# Sch_Sheet_Template.net
KiCad netlist of a schematic drawn in Altium Designer
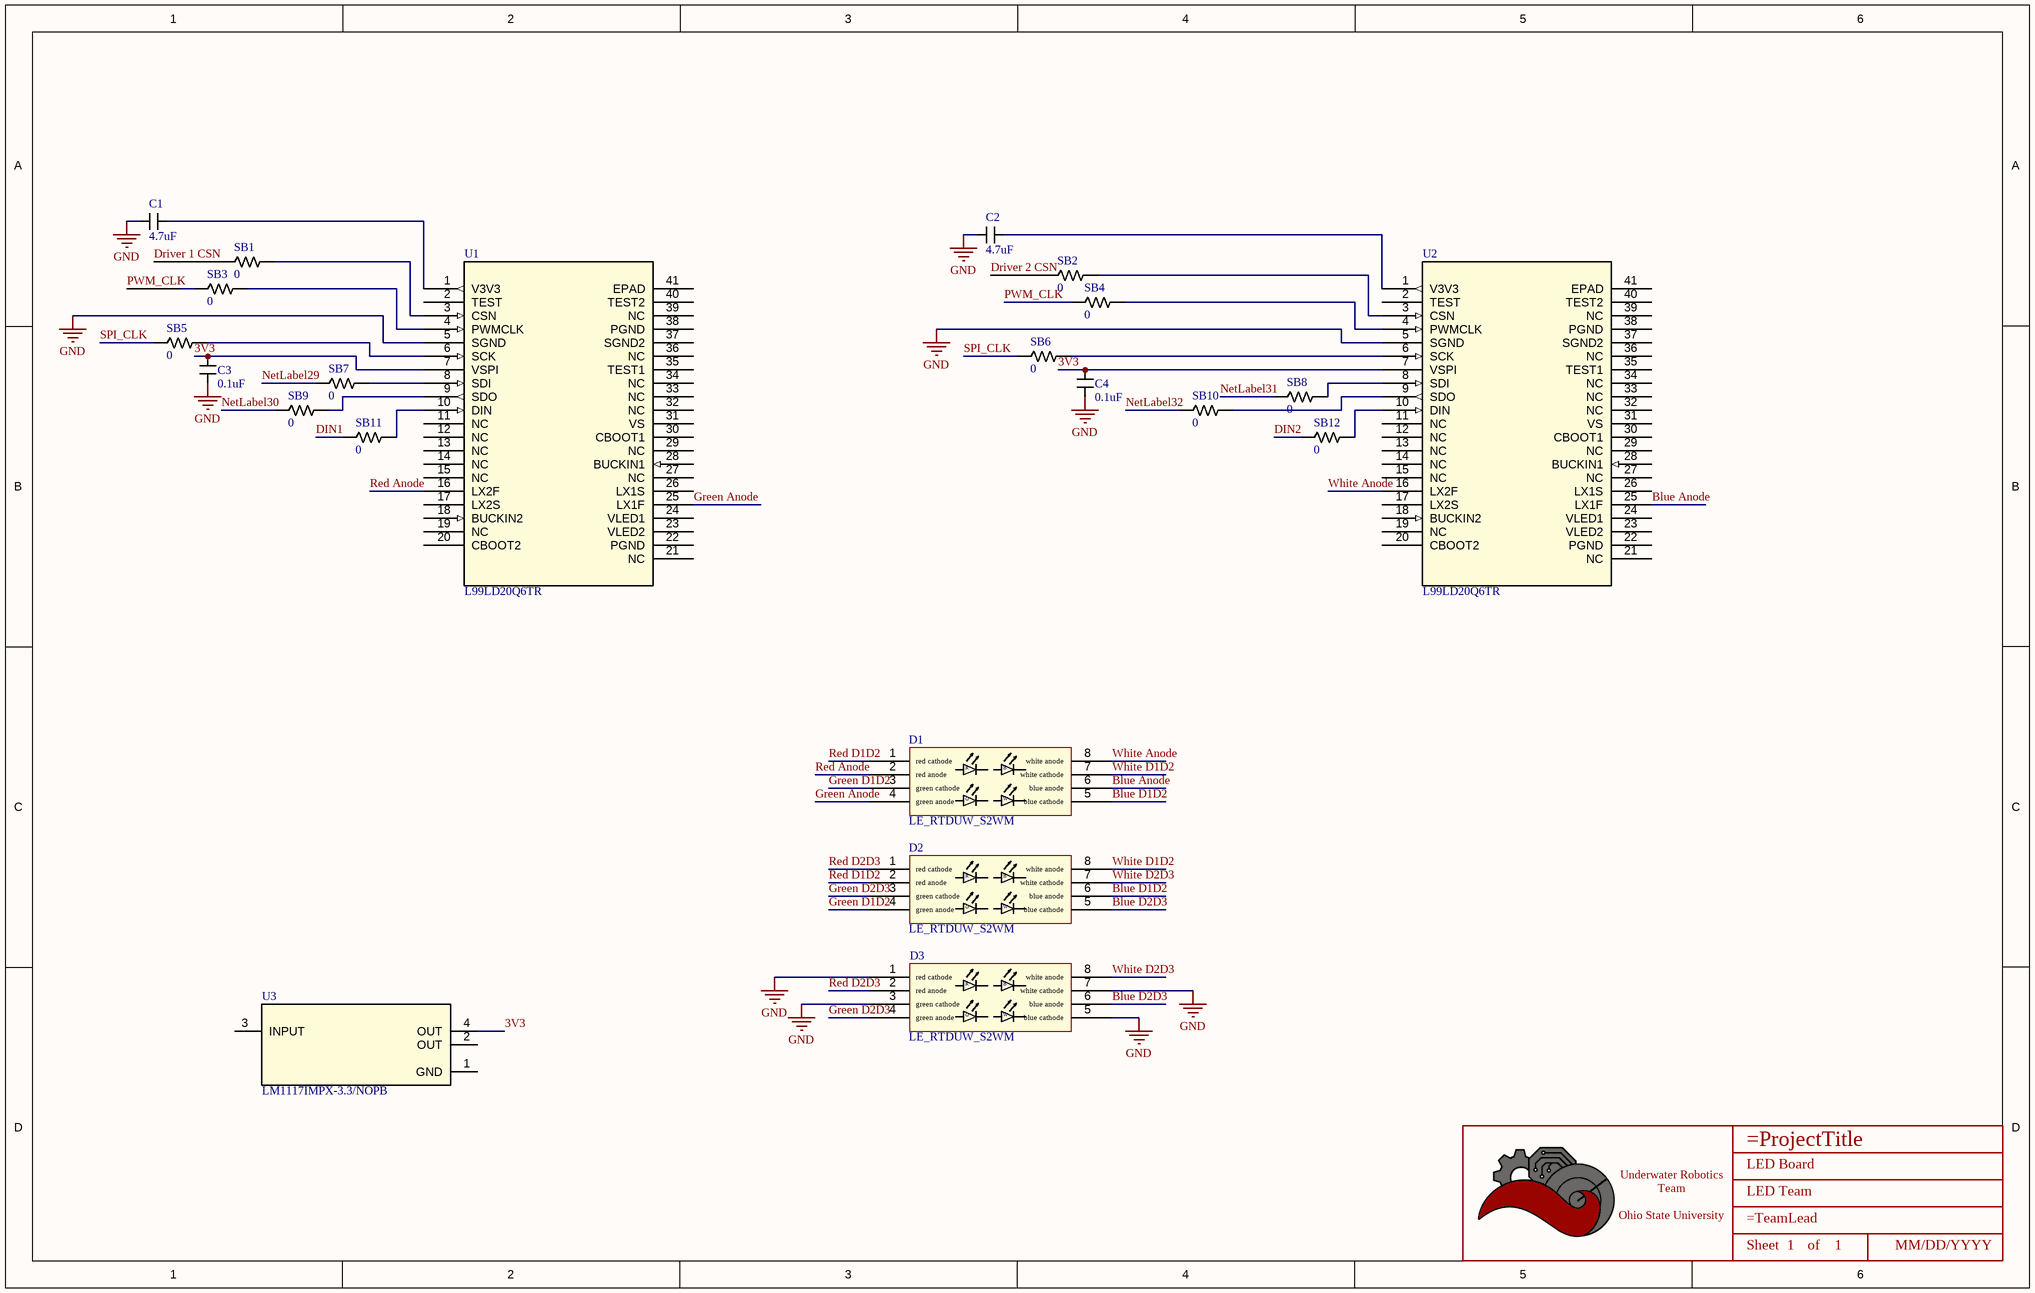
[diagram p0: Sch_Sheet_Template.SchDoc]

(export (version "E")
  (design (tool "Eeschema 10.0.6"))
  (components
    (comp (ref "*")
      (value "Title_Block")
      (footprint "LOGO")
      (description "UWRT Schematic Title Block Template\r\n\r\nCreated June 2021, Dylan Trainor")
      (libsource (lib "UWRT") (part "Title_Block"))
    )
    (comp (ref "C1")
      (value "4.7uF")
      (footprint "CAPACITOR_0603")
      (description "Cap 4.7uF 6.3V +/-10%\r\nCeramic 0603")
      (fields
        (field (name "TOLERANCE") "+/- 10%")
        (field (name "VOLTAGE") "6.3V")
        (field (name "MADE BY") "Robert Pafford")
      )
      (libsource (lib "Capacitors") (part "CAPACITOR_4.7uF_0603"))
    )
    (comp (ref "C2")
      (value "4.7uF")
      (footprint "CAPACITOR_0603")
      (description "Cap 4.7uF 6.3V +/-10%\r\nCeramic 0603")
      (fields
        (field (name "TOLERANCE") "+/- 10%")
        (field (name "VOLTAGE") "6.3V")
        (field (name "MADE BY") "Robert Pafford")
      )
      (libsource (lib "Capacitors") (part "CAPACITOR_4.7uF_0603"))
    )
    (comp (ref "C3")
      (value "0.1uF")
      (footprint "CAPACITOR_0603")
      (description "Cap 100nF 6.3V +/-10%\r\nCeramic 0603")
      (fields
        (field (name "TOLERANCE") "+/- 10%")
        (field (name "VOLTAGE") "6.3V")
        (field (name "MADE BY") "Flip B")
      )
      (libsource (lib "Capacitors") (part "CAPACITOR_0.1uF_0603_1"))
    )
    (comp (ref "C4")
      (value "0.1uF")
      (footprint "CAPACITOR_0603")
      (description "Cap 100nF 6.3V +/-10%\r\nCeramic 0603")
      (fields
        (field (name "TOLERANCE") "+/- 10%")
        (field (name "VOLTAGE") "6.3V")
        (field (name "MADE BY") "Flip B")
      )
      (libsource (lib "Capacitors") (part "CAPACITOR_0.1uF_0603_1"))
    )
    (comp (ref "D1")
      (value "LE_RTDUW_S2WM")
      (description "LED OSTAR RGBW 625/527/453NM SMD")
      (libsource (lib "Diodes") (part "LE_RTDUW_S2WM"))
    )
    (comp (ref "D2")
      (value "LE_RTDUW_S2WM")
      (description "LED OSTAR RGBW 625/527/453NM SMD")
      (libsource (lib "Diodes") (part "LE_RTDUW_S2WM"))
    )
    (comp (ref "D3")
      (value "LE_RTDUW_S2WM")
      (description "LED OSTAR RGBW 625/527/453NM SMD")
      (libsource (lib "Diodes") (part "LE_RTDUW_S2WM"))
    )
    (comp (ref "SB1")
      (value "0 Ohm Jumper No Fit")
      (footprint "RESISTOR_0603")
      (description "0 Ohm Jumper No Fit for Solder Bridge")
      (fields (field (name "VALUE  (OHMS)") "0") (field (name "MADE BY") "Robert Pafford"))
      (libsource (lib "Resistors") (part "JUMPER_0_0603"))
    )
    (comp (ref "SB2")
      (value "0 Ohm Jumper No Fit")
      (footprint "RESISTOR_0603")
      (description "0 Ohm Jumper No Fit for Solder Bridge")
      (fields (field (name "VALUE  (OHMS)") "0") (field (name "MADE BY") "Robert Pafford"))
      (libsource (lib "Resistors") (part "JUMPER_0_0603"))
    )
    (comp (ref "SB3")
      (value "0 Ohm Jumper No Fit")
      (footprint "RESISTOR_0603")
      (description "0 Ohm Jumper No Fit for Solder Bridge")
      (fields (field (name "VALUE  (OHMS)") "0") (field (name "MADE BY") "Robert Pafford"))
      (libsource (lib "Resistors") (part "JUMPER_0_0603"))
    )
    (comp (ref "SB4")
      (value "0 Ohm Jumper No Fit")
      (footprint "RESISTOR_0603")
      (description "0 Ohm Jumper No Fit for Solder Bridge")
      (fields (field (name "VALUE  (OHMS)") "0") (field (name "MADE BY") "Robert Pafford"))
      (libsource (lib "Resistors") (part "JUMPER_0_0603"))
    )
    (comp (ref "SB5")
      (value "0 Ohm Jumper No Fit")
      (footprint "RESISTOR_0603")
      (description "0 Ohm Jumper No Fit for Solder Bridge")
      (fields (field (name "VALUE  (OHMS)") "0") (field (name "MADE BY") "Robert Pafford"))
      (libsource (lib "Resistors") (part "JUMPER_0_0603"))
    )
    (comp (ref "SB6")
      (value "0 Ohm Jumper No Fit")
      (footprint "RESISTOR_0603")
      (description "0 Ohm Jumper No Fit for Solder Bridge")
      (fields (field (name "VALUE  (OHMS)") "0") (field (name "MADE BY") "Robert Pafford"))
      (libsource (lib "Resistors") (part "JUMPER_0_0603"))
    )
    (comp (ref "SB7")
      (value "0 Ohm Jumper No Fit")
      (footprint "RESISTOR_0603")
      (description "0 Ohm Jumper No Fit for Solder Bridge")
      (fields (field (name "VALUE  (OHMS)") "0") (field (name "MADE BY") "Robert Pafford"))
      (libsource (lib "Resistors") (part "JUMPER_0_0603"))
    )
    (comp (ref "SB8")
      (value "0 Ohm Jumper No Fit")
      (footprint "RESISTOR_0603")
      (description "0 Ohm Jumper No Fit for Solder Bridge")
      (fields (field (name "VALUE  (OHMS)") "0") (field (name "MADE BY") "Robert Pafford"))
      (libsource (lib "Resistors") (part "JUMPER_0_0603"))
    )
    (comp (ref "SB9")
      (value "0 Ohm Jumper No Fit")
      (footprint "RESISTOR_0603")
      (description "0 Ohm Jumper No Fit for Solder Bridge")
      (fields (field (name "VALUE  (OHMS)") "0") (field (name "MADE BY") "Robert Pafford"))
      (libsource (lib "Resistors") (part "JUMPER_0_0603"))
    )
    (comp (ref "SB10")
      (value "0 Ohm Jumper No Fit")
      (footprint "RESISTOR_0603")
      (description "0 Ohm Jumper No Fit for Solder Bridge")
      (fields (field (name "VALUE  (OHMS)") "0") (field (name "MADE BY") "Robert Pafford"))
      (libsource (lib "Resistors") (part "JUMPER_0_0603"))
    )
    (comp (ref "SB11")
      (value "0 Ohm Jumper No Fit")
      (footprint "RESISTOR_0603")
      (description "0 Ohm Jumper No Fit for Solder Bridge")
      (fields (field (name "VALUE  (OHMS)") "0") (field (name "MADE BY") "Robert Pafford"))
      (libsource (lib "Resistors") (part "JUMPER_0_0603"))
    )
    (comp (ref "SB12")
      (value "0 Ohm Jumper No Fit")
      (footprint "RESISTOR_0603")
      (description "0 Ohm Jumper No Fit for Solder Bridge")
      (fields (field (name "VALUE  (OHMS)") "0") (field (name "MADE BY") "Robert Pafford"))
      (libsource (lib "Resistors") (part "JUMPER_0_0603"))
    )
    (comp (ref "U1")
      (value "L99LD20Q6TR")
      (footprint "QFN40L_6P15X6P15X0P5_STM")
      (description "IC LED DRVR RGLTR PWM 1.5A 40QFN")
      (fields (field (name "COPYRIGHT") "Copyright (C) 2023 Ultra Librarian. All rights reserved."))
      (libsource (lib "Integrated Circuits") (part "L99LD20Q6TR"))
    )
    (comp (ref "U2")
      (value "L99LD20Q6TR")
      (footprint "QFN40L_6P15X6P15X0P5_STM")
      (description "IC LED DRVR RGLTR PWM 1.5A 40QFN")
      (fields (field (name "COPYRIGHT") "Copyright (C) 2023 Ultra Librarian. All rights reserved."))
      (libsource (lib "Integrated Circuits") (part "L99LD20Q6TR"))
    )
    (comp (ref "U3")
      (value "LM1117IMPX-3.3/NOPB")
      (footprint "SOT-223-4")
      (description "IC REG LIN 3.3V 800MA SOT223-4")
      (fields
        (field (name "PARTNUMBER") "LM1117IMP-3.3/NOPB")
        (field (name "MANUFACTURER") "Texas Instruments")
        (field (name "CREATED BY") "Dylan T")
      )
      (libsource (lib "Converter") (part "LM1117IMPX-3.3/NOPB"))
    )
  )
  (nets
    (net (code "1") (name "/3V3") (class "Default")
      (node (ref "C3") (pin "1") (pinfunction "1_1") (pintype "passive"))
      (node (ref "C4") (pin "1") (pinfunction "1_1") (pintype "passive"))
      (node (ref "U1") (pin "7") (pinfunction "VSPI_7") (pintype "passive"))
      (node (ref "U2") (pin "7") (pinfunction "VSPI_7") (pintype "passive"))
      (node (ref "U3") (pin "4") (pinfunction "OUT_4") (pintype "power_in"))
    )
    (net (code "2") (name "/Blue Anode") (class "Default")
      (node (ref "D1") (pin "6") (pinfunction "blue_anode_6") (pintype "passive"))
      (node (ref "U2") (pin "25") (pinfunction "LX1F_25") (pintype "passive"))
    )
    (net (code "3") (name "/Blue D1D2") (class "Default")
      (node (ref "D1") (pin "5") (pinfunction "blue_cathode_5") (pintype "passive"))
      (node (ref "D2") (pin "6") (pinfunction "blue_anode_6") (pintype "passive"))
    )
    (net (code "4") (name "/Blue D2D3") (class "Default")
      (node (ref "D2") (pin "5") (pinfunction "blue_cathode_5") (pintype "passive"))
      (node (ref "D3") (pin "6") (pinfunction "blue_anode_6") (pintype "passive"))
    )
    (net (code "5") (name "/DIN1") (class "Default")
      (node (ref "SB11") (pin "2") (pinfunction "2_2") (pintype "passive"))
    )
    (net (code "6") (name "/DIN2") (class "Default")
      (node (ref "SB12") (pin "2") (pinfunction "2_2") (pintype "passive"))
    )
    (net (code "9") (name "/Green Anode") (class "Default")
      (node (ref "D1") (pin "4") (pinfunction "green_anode_4") (pintype "passive"))
      (node (ref "U1") (pin "25") (pinfunction "LX1F_25") (pintype "passive"))
    )
    (net (code "10") (name "/Green D1D2") (class "Default")
      (node (ref "D1") (pin "3") (pinfunction "green_cathode_3") (pintype "passive"))
      (node (ref "D2") (pin "4") (pinfunction "green_anode_4") (pintype "passive"))
    )
    (net (code "11") (name "/Green D2D3") (class "Default")
      (node (ref "D2") (pin "3") (pinfunction "green_cathode_3") (pintype "passive"))
      (node (ref "D3") (pin "4") (pinfunction "green_anode_4") (pintype "passive"))
    )
    (net (code "12") (name "/NetLabel29") (class "Default")
      (node (ref "SB7") (pin "2") (pinfunction "2_2") (pintype "passive"))
    )
    (net (code "13") (name "/NetLabel30") (class "Default")
      (node (ref "SB9") (pin "2") (pinfunction "2_2") (pintype "passive"))
    )
    (net (code "14") (name "/NetLabel31") (class "Default")
      (node (ref "SB8") (pin "2") (pinfunction "2_2") (pintype "passive"))
    )
    (net (code "15") (name "/NetLabel32") (class "Default")
      (node (ref "SB10") (pin "2") (pinfunction "2_2") (pintype "passive"))
    )
    (net (code "16") (name "/PWM_CLK") (class "Default")
      (node (ref "SB4") (pin "2") (pinfunction "2_2") (pintype "passive"))
    )
    (net (code "17") (name "/Red Anode") (class "Default")
      (node (ref "D1") (pin "2") (pinfunction "red_anode_2") (pintype "passive"))
      (node (ref "U1") (pin "16") (pinfunction "LX2F_16") (pintype "passive"))
    )
    (net (code "18") (name "/Red D1D2") (class "Default")
      (node (ref "D1") (pin "1") (pinfunction "red_cathode_1") (pintype "passive"))
      (node (ref "D2") (pin "2") (pinfunction "red_anode_2") (pintype "passive"))
    )
    (net (code "19") (name "/Red D2D3") (class "Default")
      (node (ref "D2") (pin "1") (pinfunction "red_cathode_1") (pintype "passive"))
      (node (ref "D3") (pin "2") (pinfunction "red_anode_2") (pintype "passive"))
    )
    (net (code "20") (name "/SPI_CLK") (class "Default")
      (node (ref "SB5") (pin "2") (pinfunction "2_2") (pintype "passive"))
      (node (ref "SB6") (pin "2") (pinfunction "2_2") (pintype "passive"))
    )
    (net (code "21") (name "/White Anode") (class "Default")
      (node (ref "D1") (pin "8") (pinfunction "white_anode_8") (pintype "passive"))
      (node (ref "U2") (pin "16") (pinfunction "LX2F_16") (pintype "passive"))
    )
    (net (code "22") (name "/White D1D2") (class "Default")
      (node (ref "D1") (pin "7") (pinfunction "white_cathode_7") (pintype "passive"))
      (node (ref "D2") (pin "8") (pinfunction "white_anode_8") (pintype "passive"))
    )
    (net (code "23") (name "/White D2D3") (class "Default")
      (node (ref "D2") (pin "7") (pinfunction "white_cathode_7") (pintype "passive"))
      (node (ref "D3") (pin "8") (pinfunction "white_anode_8") (pintype "passive"))
    )
    (net (code "24") (name "GND") (class "Default")
      (node (ref "C1") (pin "2") (pinfunction "2_2") (pintype "passive"))
      (node (ref "C2") (pin "2") (pinfunction "2_2") (pintype "passive"))
      (node (ref "C3") (pin "2") (pinfunction "2_2") (pintype "passive"))
      (node (ref "C4") (pin "2") (pinfunction "2_2") (pintype "passive"))
      (node (ref "D3") (pin "1") (pinfunction "red_cathode_1") (pintype "passive"))
      (node (ref "D3") (pin "3") (pinfunction "green_cathode_3") (pintype "passive"))
      (node (ref "D3") (pin "5") (pinfunction "blue_cathode_5") (pintype "passive"))
      (node (ref "D3") (pin "7") (pinfunction "white_cathode_7") (pintype "passive"))
      (node (ref "U1") (pin "5") (pinfunction "SGND_5") (pintype "power_in"))
      (node (ref "U2") (pin "5") (pinfunction "SGND_5") (pintype "power_in"))
    )
    (net (code "25") (name "Net-(U1-CSN)") (class "Default")
      (node (ref "SB1") (pin "1") (pinfunction "1_1") (pintype "passive"))
      (node (ref "U1") (pin "3") (pinfunction "CSN_3") (pintype "input"))
    )
    (net (code "26") (name "Net-(U1-DIN)") (class "Default")
      (node (ref "SB11") (pin "1") (pinfunction "1_1") (pintype "passive"))
      (node (ref "U1") (pin "10") (pinfunction "DIN_10") (pintype "input"))
    )
    (net (code "27") (name "Net-(U1-PWMCLK)") (class "Default")
      (node (ref "SB3") (pin "1") (pinfunction "1_1") (pintype "passive"))
      (node (ref "U1") (pin "4") (pinfunction "PWMCLK_4") (pintype "input"))
    )
    (net (code "28") (name "Net-(U1-SCK)") (class "Default")
      (node (ref "SB5") (pin "1") (pinfunction "1_1") (pintype "passive"))
      (node (ref "U1") (pin "6") (pinfunction "SCK_6") (pintype "input"))
    )
    (net (code "29") (name "Net-(U1-SDI)") (class "Default")
      (node (ref "SB7") (pin "1") (pinfunction "1_1") (pintype "passive"))
      (node (ref "U1") (pin "8") (pinfunction "SDI_8") (pintype "input"))
    )
    (net (code "30") (name "Net-(U1-SDO)") (class "Default")
      (node (ref "SB9") (pin "1") (pinfunction "1_1") (pintype "passive"))
      (node (ref "U1") (pin "9") (pinfunction "SDO_9") (pintype "output"))
    )
    (net (code "31") (name "Net-(U1-V3V3)") (class "Default")
      (node (ref "C1") (pin "1") (pinfunction "1_1") (pintype "passive"))
      (node (ref "U1") (pin "1") (pinfunction "V3V3_1") (pintype "output"))
    )
    (net (code "32") (name "Net-(U2-CSN)") (class "Default")
      (node (ref "SB2") (pin "1") (pinfunction "1_1") (pintype "passive"))
      (node (ref "U2") (pin "3") (pinfunction "CSN_3") (pintype "input"))
    )
    (net (code "33") (name "Net-(U2-DIN)") (class "Default")
      (node (ref "SB12") (pin "1") (pinfunction "1_1") (pintype "passive"))
      (node (ref "U2") (pin "10") (pinfunction "DIN_10") (pintype "input"))
    )
    (net (code "34") (name "Net-(U2-PWMCLK)") (class "Default")
      (node (ref "SB4") (pin "1") (pinfunction "1_1") (pintype "passive"))
      (node (ref "U2") (pin "4") (pinfunction "PWMCLK_4") (pintype "input"))
    )
    (net (code "35") (name "Net-(U2-SCK)") (class "Default")
      (node (ref "SB6") (pin "1") (pinfunction "1_1") (pintype "passive"))
      (node (ref "U2") (pin "6") (pinfunction "SCK_6") (pintype "input"))
    )
    (net (code "36") (name "Net-(U2-SDI)") (class "Default")
      (node (ref "SB8") (pin "1") (pinfunction "1_1") (pintype "passive"))
      (node (ref "U2") (pin "8") (pinfunction "SDI_8") (pintype "input"))
    )
    (net (code "37") (name "Net-(U2-SDO)") (class "Default")
      (node (ref "SB10") (pin "1") (pinfunction "1_1") (pintype "passive"))
      (node (ref "U2") (pin "9") (pinfunction "SDO_9") (pintype "output"))
    )
    (net (code "38") (name "Net-(U2-V3V3)") (class "Default")
      (node (ref "C2") (pin "1") (pinfunction "1_1") (pintype "passive"))
      (node (ref "U2") (pin "1") (pinfunction "V3V3_1") (pintype "output"))
    )
    (net (code "39") (name "unconnected-(SB1-Pad2)") (class "Default")
      (node (ref "SB1") (pin "2") (pinfunction "2_2") (pintype "passive"))
    )
    (net (code "40") (name "unconnected-(SB2-Pad2)") (class "Default")
      (node (ref "SB2") (pin "2") (pinfunction "2_2") (pintype "passive"))
    )
    (net (code "41") (name "unconnected-(SB3-Pad2)") (class "Default")
      (node (ref "SB3") (pin "2") (pinfunction "2_2") (pintype "passive"))
    )
    (net (code "42") (name "unconnected-(U1-BUCKIN1-Pad28)") (class "Default")
      (node (ref "U1") (pin "28") (pinfunction "BUCKIN1_28") (pintype "input"))
    )
    (net (code "43") (name "unconnected-(U1-BUCKIN2-Pad18)") (class "Default")
      (node (ref "U1") (pin "18") (pinfunction "BUCKIN2_18") (pintype "input"))
    )
    (net (code "44") (name "unconnected-(U1-CBOOT1-Pad30)") (class "Default")
      (node (ref "U1") (pin "30") (pinfunction "CBOOT1_30") (pintype "passive"))
    )
    (net (code "45") (name "unconnected-(U1-CBOOT2-Pad20)") (class "Default")
      (node (ref "U1") (pin "20") (pinfunction "CBOOT2_20") (pintype "passive"))
    )
    (net (code "46") (name "unconnected-(U1-EPAD-Pad41)") (class "Default")
      (node (ref "U1") (pin "41") (pinfunction "EPAD_41") (pintype "power_in"))
    )
    (net (code "47") (name "unconnected-(U1-LX1S-Pad26)") (class "Default")
      (node (ref "U1") (pin "26") (pinfunction "LX1S_26") (pintype "passive"))
    )
    (net (code "48") (name "unconnected-(U1-LX2S-Pad17)") (class "Default")
      (node (ref "U1") (pin "17") (pinfunction "LX2S_17") (pintype "passive"))
    )
    (net (code "49") (name "unconnected-(U1-NC-Pad11)") (class "Default")
      (node (ref "U1") (pin "11") (pinfunction "NC_11") (pintype "passive"))
    )
    (net (code "50") (name "unconnected-(U1-NC-Pad12)") (class "Default")
      (node (ref "U1") (pin "12") (pinfunction "NC_12") (pintype "passive"))
    )
    (net (code "51") (name "unconnected-(U1-NC-Pad13)") (class "Default")
      (node (ref "U1") (pin "13") (pinfunction "NC_13") (pintype "passive"))
    )
    (net (code "52") (name "unconnected-(U1-NC-Pad14)") (class "Default")
      (node (ref "U1") (pin "14") (pinfunction "NC_14") (pintype "passive"))
    )
    (net (code "53") (name "unconnected-(U1-NC-Pad15)") (class "Default")
      (node (ref "U1") (pin "15") (pinfunction "NC_15") (pintype "passive"))
    )
    (net (code "54") (name "unconnected-(U1-NC-Pad19)") (class "Default")
      (node (ref "U1") (pin "19") (pinfunction "NC_19") (pintype "passive"))
    )
    (net (code "55") (name "unconnected-(U1-NC-Pad21)") (class "Default")
      (node (ref "U1") (pin "21") (pinfunction "NC_21") (pintype "passive"))
    )
    (net (code "56") (name "unconnected-(U1-NC-Pad27)") (class "Default")
      (node (ref "U1") (pin "27") (pinfunction "NC_27") (pintype "passive"))
    )
    (net (code "57") (name "unconnected-(U1-NC-Pad29)") (class "Default")
      (node (ref "U1") (pin "29") (pinfunction "NC_29") (pintype "passive"))
    )
    (net (code "58") (name "unconnected-(U1-NC-Pad32)") (class "Default")
      (node (ref "U1") (pin "32") (pinfunction "NC_32") (pintype "passive"))
    )
    (net (code "59") (name "unconnected-(U1-NC-Pad33)") (class "Default")
      (node (ref "U1") (pin "33") (pinfunction "NC_33") (pintype "passive"))
    )
    (net (code "60") (name "unconnected-(U1-NC-Pad34)") (class "Default")
      (node (ref "U1") (pin "34") (pinfunction "NC_34") (pintype "passive"))
    )
    (net (code "61") (name "unconnected-(U1-NC-Pad36)") (class "Default")
      (node (ref "U1") (pin "36") (pinfunction "NC_36") (pintype "passive"))
    )
    (net (code "62") (name "unconnected-(U1-NC-Pad39)") (class "Default")
      (node (ref "U1") (pin "39") (pinfunction "NC_39") (pintype "passive"))
    )
    (net (code "63") (name "unconnected-(U1-PGND-Pad22)") (class "Default")
      (node (ref "U1") (pin "22") (pinfunction "PGND_22") (pintype "power_in"))
    )
    (net (code "64") (name "unconnected-(U1-PGND-Pad38)") (class "Default")
      (node (ref "U1") (pin "38") (pinfunction "PGND_38") (pintype "power_in"))
    )
    (net (code "65") (name "unconnected-(U1-SGND2-Pad37)") (class "Default")
      (node (ref "U1") (pin "37") (pinfunction "SGND2_37") (pintype "power_in"))
    )
    (net (code "66") (name "unconnected-(U1-TEST-Pad2)") (class "Default")
      (node (ref "U1") (pin "2") (pinfunction "TEST_2") (pintype "passive"))
    )
    (net (code "67") (name "unconnected-(U1-TEST1-Pad35)") (class "Default")
      (node (ref "U1") (pin "35") (pinfunction "TEST1_35") (pintype "passive"))
    )
    (net (code "68") (name "unconnected-(U1-TEST2-Pad40)") (class "Default")
      (node (ref "U1") (pin "40") (pinfunction "TEST2_40") (pintype "passive"))
    )
    (net (code "69") (name "unconnected-(U1-VLED1-Pad24)") (class "Default")
      (node (ref "U1") (pin "24") (pinfunction "VLED1_24") (pintype "passive"))
    )
    (net (code "70") (name "unconnected-(U1-VLED2-Pad23)") (class "Default")
      (node (ref "U1") (pin "23") (pinfunction "VLED2_23") (pintype "passive"))
    )
    (net (code "71") (name "unconnected-(U1-VS-Pad31)") (class "Default")
      (node (ref "U1") (pin "31") (pinfunction "VS_31") (pintype "passive"))
    )
    (net (code "72") (name "unconnected-(U2-BUCKIN1-Pad28)") (class "Default")
      (node (ref "U2") (pin "28") (pinfunction "BUCKIN1_28") (pintype "input"))
    )
    (net (code "73") (name "unconnected-(U2-BUCKIN2-Pad18)") (class "Default")
      (node (ref "U2") (pin "18") (pinfunction "BUCKIN2_18") (pintype "input"))
    )
    (net (code "74") (name "unconnected-(U2-CBOOT1-Pad30)") (class "Default")
      (node (ref "U2") (pin "30") (pinfunction "CBOOT1_30") (pintype "passive"))
    )
    (net (code "75") (name "unconnected-(U2-CBOOT2-Pad20)") (class "Default")
      (node (ref "U2") (pin "20") (pinfunction "CBOOT2_20") (pintype "passive"))
    )
    (net (code "76") (name "unconnected-(U2-EPAD-Pad41)") (class "Default")
      (node (ref "U2") (pin "41") (pinfunction "EPAD_41") (pintype "power_in"))
    )
    (net (code "77") (name "unconnected-(U2-LX1S-Pad26)") (class "Default")
      (node (ref "U2") (pin "26") (pinfunction "LX1S_26") (pintype "passive"))
    )
    (net (code "78") (name "unconnected-(U2-LX2S-Pad17)") (class "Default")
      (node (ref "U2") (pin "17") (pinfunction "LX2S_17") (pintype "passive"))
    )
    (net (code "79") (name "unconnected-(U2-NC-Pad11)") (class "Default")
      (node (ref "U2") (pin "11") (pinfunction "NC_11") (pintype "passive"))
    )
    (net (code "80") (name "unconnected-(U2-NC-Pad12)") (class "Default")
      (node (ref "U2") (pin "12") (pinfunction "NC_12") (pintype "passive"))
    )
    (net (code "81") (name "unconnected-(U2-NC-Pad13)") (class "Default")
      (node (ref "U2") (pin "13") (pinfunction "NC_13") (pintype "passive"))
    )
    (net (code "82") (name "unconnected-(U2-NC-Pad14)") (class "Default")
      (node (ref "U2") (pin "14") (pinfunction "NC_14") (pintype "passive"))
    )
    (net (code "83") (name "unconnected-(U2-NC-Pad15)") (class "Default")
      (node (ref "U2") (pin "15") (pinfunction "NC_15") (pintype "passive"))
    )
    (net (code "84") (name "unconnected-(U2-NC-Pad19)") (class "Default")
      (node (ref "U2") (pin "19") (pinfunction "NC_19") (pintype "passive"))
    )
    (net (code "85") (name "unconnected-(U2-NC-Pad21)") (class "Default")
      (node (ref "U2") (pin "21") (pinfunction "NC_21") (pintype "passive"))
    )
    (net (code "86") (name "unconnected-(U2-NC-Pad27)") (class "Default")
      (node (ref "U2") (pin "27") (pinfunction "NC_27") (pintype "passive"))
    )
    (net (code "87") (name "unconnected-(U2-NC-Pad29)") (class "Default")
      (node (ref "U2") (pin "29") (pinfunction "NC_29") (pintype "passive"))
    )
    (net (code "88") (name "unconnected-(U2-NC-Pad32)") (class "Default")
      (node (ref "U2") (pin "32") (pinfunction "NC_32") (pintype "passive"))
    )
    (net (code "89") (name "unconnected-(U2-NC-Pad33)") (class "Default")
      (node (ref "U2") (pin "33") (pinfunction "NC_33") (pintype "passive"))
    )
    (net (code "90") (name "unconnected-(U2-NC-Pad34)") (class "Default")
      (node (ref "U2") (pin "34") (pinfunction "NC_34") (pintype "passive"))
    )
    (net (code "91") (name "unconnected-(U2-NC-Pad36)") (class "Default")
      (node (ref "U2") (pin "36") (pinfunction "NC_36") (pintype "passive"))
    )
    (net (code "92") (name "unconnected-(U2-NC-Pad39)") (class "Default")
      (node (ref "U2") (pin "39") (pinfunction "NC_39") (pintype "passive"))
    )
    (net (code "93") (name "unconnected-(U2-PGND-Pad22)") (class "Default")
      (node (ref "U2") (pin "22") (pinfunction "PGND_22") (pintype "power_in"))
    )
    (net (code "94") (name "unconnected-(U2-PGND-Pad38)") (class "Default")
      (node (ref "U2") (pin "38") (pinfunction "PGND_38") (pintype "power_in"))
    )
    (net (code "95") (name "unconnected-(U2-SGND2-Pad37)") (class "Default")
      (node (ref "U2") (pin "37") (pinfunction "SGND2_37") (pintype "power_in"))
    )
    (net (code "96") (name "unconnected-(U2-TEST-Pad2)") (class "Default")
      (node (ref "U2") (pin "2") (pinfunction "TEST_2") (pintype "passive"))
    )
    (net (code "97") (name "unconnected-(U2-TEST1-Pad35)") (class "Default")
      (node (ref "U2") (pin "35") (pinfunction "TEST1_35") (pintype "passive"))
    )
    (net (code "98") (name "unconnected-(U2-TEST2-Pad40)") (class "Default")
      (node (ref "U2") (pin "40") (pinfunction "TEST2_40") (pintype "passive"))
    )
    (net (code "99") (name "unconnected-(U2-VLED1-Pad24)") (class "Default")
      (node (ref "U2") (pin "24") (pinfunction "VLED1_24") (pintype "passive"))
    )
    (net (code "100") (name "unconnected-(U2-VLED2-Pad23)") (class "Default")
      (node (ref "U2") (pin "23") (pinfunction "VLED2_23") (pintype "passive"))
    )
    (net (code "101") (name "unconnected-(U2-VS-Pad31)") (class "Default")
      (node (ref "U2") (pin "31") (pinfunction "VS_31") (pintype "passive"))
    )
    (net (code "102") (name "unconnected-(U3-GND-Pad1)") (class "Default")
      (node (ref "U3") (pin "1") (pinfunction "GND_1") (pintype "power_in"))
    )
    (net (code "103") (name "unconnected-(U3-INPUT-Pad3)") (class "Default")
      (node (ref "U3") (pin "3") (pinfunction "INPUT_3") (pintype "power_in"))
    )
    (net (code "104") (name "unconnected-(U3-OUT-Pad2)") (class "Default")
      (node (ref "U3") (pin "2") (pinfunction "OUT_2") (pintype "power_in"))
    )
  )
)
